# INPUT_8CH.net
KiCad netlist of a schematic drawn in Altium Designer
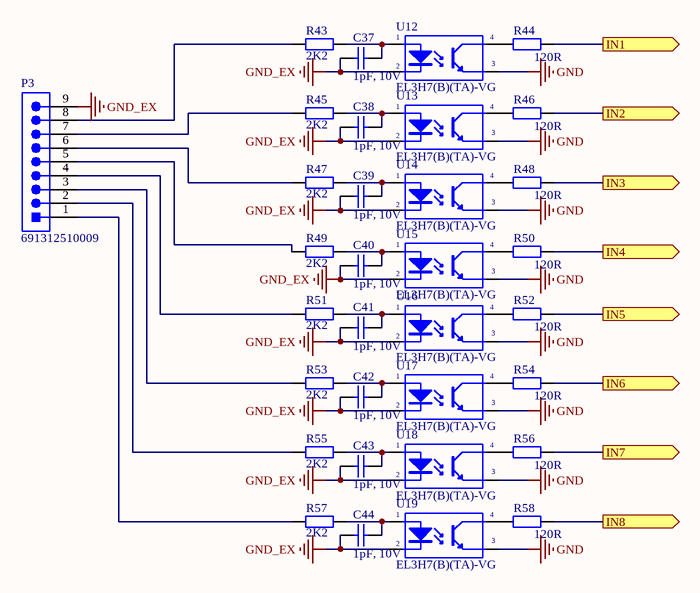
[diagram p0: INPUT_8CH.SchDoc]

(export (version "E")
  (design (tool "Eeschema 10.0.6"))
  (components
    (comp (ref "C37")
      (value "1pF, 10V")
      (footprint "CAP_0805")
      (description "WCAP-CSGP General Purpose Ceramic Capacitors")
      (fields (field (name "PART NUMBER") "885012005001") (field (name "PUBLISHER") "Wurth Elektronik"))
      (libsource (lib "ThanhNhan") (part "CAP_SMD"))
    )
    (comp (ref "C38")
      (value "1pF, 10V")
      (footprint "CAP_0805")
      (description "WCAP-CSGP General Purpose Ceramic Capacitors")
      (fields (field (name "PART NUMBER") "885012005001") (field (name "PUBLISHER") "Wurth Elektronik"))
      (libsource (lib "ThanhNhan") (part "CAP_SMD"))
    )
    (comp (ref "C39")
      (value "1pF, 10V")
      (footprint "CAP_0805")
      (description "WCAP-CSGP General Purpose Ceramic Capacitors")
      (fields (field (name "PART NUMBER") "885012005001") (field (name "PUBLISHER") "Wurth Elektronik"))
      (libsource (lib "ThanhNhan") (part "CAP_SMD"))
    )
    (comp (ref "C40")
      (value "1pF, 10V")
      (footprint "CAP_0805")
      (description "WCAP-CSGP General Purpose Ceramic Capacitors")
      (fields (field (name "PART NUMBER") "885012005001") (field (name "PUBLISHER") "Wurth Elektronik"))
      (libsource (lib "ThanhNhan") (part "CAP_SMD"))
    )
    (comp (ref "C41")
      (value "1pF, 10V")
      (footprint "CAP_0805")
      (description "WCAP-CSGP General Purpose Ceramic Capacitors")
      (fields (field (name "PART NUMBER") "885012005001") (field (name "PUBLISHER") "Wurth Elektronik"))
      (libsource (lib "ThanhNhan") (part "CAP_SMD"))
    )
    (comp (ref "C42")
      (value "1pF, 10V")
      (footprint "CAP_0805")
      (description "WCAP-CSGP General Purpose Ceramic Capacitors")
      (fields (field (name "PART NUMBER") "885012005001") (field (name "PUBLISHER") "Wurth Elektronik"))
      (libsource (lib "ThanhNhan") (part "CAP_SMD"))
    )
    (comp (ref "C43")
      (value "1pF, 10V")
      (footprint "CAP_0805")
      (description "WCAP-CSGP General Purpose Ceramic Capacitors")
      (fields (field (name "PART NUMBER") "885012005001") (field (name "PUBLISHER") "Wurth Elektronik"))
      (libsource (lib "ThanhNhan") (part "CAP_SMD"))
    )
    (comp (ref "C44")
      (value "1pF, 10V")
      (footprint "CAP_0805")
      (description "WCAP-CSGP General Purpose Ceramic Capacitors")
      (fields (field (name "PART NUMBER") "885012005001") (field (name "PUBLISHER") "Wurth Elektronik"))
      (libsource (lib "ThanhNhan") (part "CAP_SMD"))
    )
    (comp (ref "P3")
      (value "691312510009")
      (footprint "691312510009")
      (description "WR-TBL Serie 312 Open Horizontal PCB Header, Pluggable, THT, pitch 5.08mm, 9p")
      (fields (field (name "MANUFACTURER") "Wurth Elektronik"))
      (libsource (lib "Integrated_Library1") (part "691312510009"))
    )
    (comp (ref "R43")
      (value "2K2")
      (footprint "RES_1206")
      (description "WRIS-KSKE SMT Thick Film Resistor, 0.125W")
      (fields
        (field (name "MANUFACTURER") "Wurth Elektronik")
        (field (name "MANUFACTURER PART NUMBER") "560050310010")
      )
      (libsource (lib "ThanhNhan") (part "RES_SMD"))
    )
    (comp (ref "R44")
      (value "120R")
      (footprint "RES_0603")
      (description "WRIS-KSKE SMT Thick Film Resistor, 0.125W")
      (fields
        (field (name "MANUFACTURER") "Wurth Elektronik")
        (field (name "MANUFACTURER PART NUMBER") "560050310010")
      )
      (libsource (lib "ThanhNhan") (part "RES_SMD"))
    )
    (comp (ref "R45")
      (value "2K2")
      (footprint "RES_1206")
      (description "WRIS-KSKE SMT Thick Film Resistor, 0.125W")
      (fields
        (field (name "MANUFACTURER") "Wurth Elektronik")
        (field (name "MANUFACTURER PART NUMBER") "560050310010")
      )
      (libsource (lib "ThanhNhan") (part "RES_SMD"))
    )
    (comp (ref "R46")
      (value "120R")
      (footprint "RES_0603")
      (description "WRIS-KSKE SMT Thick Film Resistor, 0.125W")
      (fields
        (field (name "MANUFACTURER") "Wurth Elektronik")
        (field (name "MANUFACTURER PART NUMBER") "560050310010")
      )
      (libsource (lib "ThanhNhan") (part "RES_SMD"))
    )
    (comp (ref "R47")
      (value "2K2")
      (footprint "RES_1206")
      (description "WRIS-KSKE SMT Thick Film Resistor, 0.125W")
      (fields
        (field (name "MANUFACTURER") "Wurth Elektronik")
        (field (name "MANUFACTURER PART NUMBER") "560050310010")
      )
      (libsource (lib "ThanhNhan") (part "RES_SMD"))
    )
    (comp (ref "R48")
      (value "120R")
      (footprint "RES_0603")
      (description "WRIS-KSKE SMT Thick Film Resistor, 0.125W")
      (fields
        (field (name "MANUFACTURER") "Wurth Elektronik")
        (field (name "MANUFACTURER PART NUMBER") "560050310010")
      )
      (libsource (lib "ThanhNhan") (part "RES_SMD"))
    )
    (comp (ref "R49")
      (value "2K2")
      (footprint "RES_1206")
      (description "WRIS-KSKE SMT Thick Film Resistor, 0.125W")
      (fields
        (field (name "MANUFACTURER") "Wurth Elektronik")
        (field (name "MANUFACTURER PART NUMBER") "560050310010")
      )
      (libsource (lib "ThanhNhan") (part "RES_SMD"))
    )
    (comp (ref "R50")
      (value "120R")
      (footprint "RES_0603")
      (description "WRIS-KSKE SMT Thick Film Resistor, 0.125W")
      (fields
        (field (name "MANUFACTURER") "Wurth Elektronik")
        (field (name "MANUFACTURER PART NUMBER") "560050310010")
      )
      (libsource (lib "ThanhNhan") (part "RES_SMD"))
    )
    (comp (ref "R51")
      (value "2K2")
      (footprint "RES_1206")
      (description "WRIS-KSKE SMT Thick Film Resistor, 0.125W")
      (fields
        (field (name "MANUFACTURER") "Wurth Elektronik")
        (field (name "MANUFACTURER PART NUMBER") "560050310010")
      )
      (libsource (lib "ThanhNhan") (part "RES_SMD"))
    )
    (comp (ref "R52")
      (value "120R")
      (footprint "RES_0603")
      (description "WRIS-KSKE SMT Thick Film Resistor, 0.125W")
      (fields
        (field (name "MANUFACTURER") "Wurth Elektronik")
        (field (name "MANUFACTURER PART NUMBER") "560050310010")
      )
      (libsource (lib "ThanhNhan") (part "RES_SMD"))
    )
    (comp (ref "R53")
      (value "2K2")
      (footprint "RES_1206")
      (description "WRIS-KSKE SMT Thick Film Resistor, 0.125W")
      (fields
        (field (name "MANUFACTURER") "Wurth Elektronik")
        (field (name "MANUFACTURER PART NUMBER") "560050310010")
      )
      (libsource (lib "ThanhNhan") (part "RES_SMD"))
    )
    (comp (ref "R54")
      (value "120R")
      (footprint "RES_0603")
      (description "WRIS-KSKE SMT Thick Film Resistor, 0.125W")
      (fields
        (field (name "MANUFACTURER") "Wurth Elektronik")
        (field (name "MANUFACTURER PART NUMBER") "560050310010")
      )
      (libsource (lib "ThanhNhan") (part "RES_SMD"))
    )
    (comp (ref "R55")
      (value "2K2")
      (footprint "RES_1206")
      (description "WRIS-KSKE SMT Thick Film Resistor, 0.125W")
      (fields
        (field (name "MANUFACTURER") "Wurth Elektronik")
        (field (name "MANUFACTURER PART NUMBER") "560050310010")
      )
      (libsource (lib "ThanhNhan") (part "RES_SMD"))
    )
    (comp (ref "R56")
      (value "120R")
      (footprint "RES_0603")
      (description "WRIS-KSKE SMT Thick Film Resistor, 0.125W")
      (fields
        (field (name "MANUFACTURER") "Wurth Elektronik")
        (field (name "MANUFACTURER PART NUMBER") "560050310010")
      )
      (libsource (lib "ThanhNhan") (part "RES_SMD"))
    )
    (comp (ref "R57")
      (value "2K2")
      (footprint "RES_1206")
      (description "WRIS-KSKE SMT Thick Film Resistor, 0.125W")
      (fields
        (field (name "MANUFACTURER") "Wurth Elektronik")
        (field (name "MANUFACTURER PART NUMBER") "560050310010")
      )
      (libsource (lib "ThanhNhan") (part "RES_SMD"))
    )
    (comp (ref "R58")
      (value "120R")
      (footprint "RES_0603")
      (description "WRIS-KSKE SMT Thick Film Resistor, 0.125W")
      (fields
        (field (name "MANUFACTURER") "Wurth Elektronik")
        (field (name "MANUFACTURER PART NUMBER") "560050310010")
      )
      (libsource (lib "ThanhNhan") (part "RES_SMD"))
    )
    (comp (ref "U12")
      (value "UNK_Everlight_EL3H7_B_TA_-VG_eec")
      (footprint "Everlight_EL3H7_B_TA_-VG_0")
      (description "UNK OPTOISOLATOR 3.75KV TRANS 4-SSOP")
      (fields
        (field (name "MANUFACTURER") "Everlight")
        (field (name "MOUSER PART NUMBER") "638-EL3H7BTAVG")
        (field (name "PART NUMBER") "EL3H7(B)(TA)-VG")
      )
      (libsource (lib "myAltium") (part "UNK_Everlight_EL3H7_B_TA_-VG_eec"))
    )
    (comp (ref "U13")
      (value "UNK_Everlight_EL3H7_B_TA_-VG_eec")
      (footprint "Everlight_EL3H7_B_TA_-VG_0")
      (description "UNK OPTOISOLATOR 3.75KV TRANS 4-SSOP")
      (fields
        (field (name "MANUFACTURER") "Everlight")
        (field (name "MOUSER PART NUMBER") "638-EL3H7BTAVG")
        (field (name "PART NUMBER") "EL3H7(B)(TA)-VG")
      )
      (libsource (lib "myAltium") (part "UNK_Everlight_EL3H7_B_TA_-VG_eec"))
    )
    (comp (ref "U14")
      (value "UNK_Everlight_EL3H7_B_TA_-VG_eec")
      (footprint "Everlight_EL3H7_B_TA_-VG_0")
      (description "UNK OPTOISOLATOR 3.75KV TRANS 4-SSOP")
      (fields
        (field (name "MANUFACTURER") "Everlight")
        (field (name "MOUSER PART NUMBER") "638-EL3H7BTAVG")
        (field (name "PART NUMBER") "EL3H7(B)(TA)-VG")
      )
      (libsource (lib "myAltium") (part "UNK_Everlight_EL3H7_B_TA_-VG_eec"))
    )
    (comp (ref "U15")
      (value "UNK_Everlight_EL3H7_B_TA_-VG_eec")
      (footprint "Everlight_EL3H7_B_TA_-VG_0")
      (description "UNK OPTOISOLATOR 3.75KV TRANS 4-SSOP")
      (fields
        (field (name "MANUFACTURER") "Everlight")
        (field (name "MOUSER PART NUMBER") "638-EL3H7BTAVG")
        (field (name "PART NUMBER") "EL3H7(B)(TA)-VG")
      )
      (libsource (lib "myAltium") (part "UNK_Everlight_EL3H7_B_TA_-VG_eec"))
    )
    (comp (ref "U16")
      (value "UNK_Everlight_EL3H7_B_TA_-VG_eec")
      (footprint "Everlight_EL3H7_B_TA_-VG_0")
      (description "UNK OPTOISOLATOR 3.75KV TRANS 4-SSOP")
      (fields
        (field (name "MANUFACTURER") "Everlight")
        (field (name "MOUSER PART NUMBER") "638-EL3H7BTAVG")
        (field (name "PART NUMBER") "EL3H7(B)(TA)-VG")
      )
      (libsource (lib "myAltium") (part "UNK_Everlight_EL3H7_B_TA_-VG_eec"))
    )
    (comp (ref "U17")
      (value "UNK_Everlight_EL3H7_B_TA_-VG_eec")
      (footprint "Everlight_EL3H7_B_TA_-VG_0")
      (description "UNK OPTOISOLATOR 3.75KV TRANS 4-SSOP")
      (fields
        (field (name "MANUFACTURER") "Everlight")
        (field (name "MOUSER PART NUMBER") "638-EL3H7BTAVG")
        (field (name "PART NUMBER") "EL3H7(B)(TA)-VG")
      )
      (libsource (lib "myAltium") (part "UNK_Everlight_EL3H7_B_TA_-VG_eec"))
    )
    (comp (ref "U18")
      (value "UNK_Everlight_EL3H7_B_TA_-VG_eec")
      (footprint "Everlight_EL3H7_B_TA_-VG_0")
      (description "UNK OPTOISOLATOR 3.75KV TRANS 4-SSOP")
      (fields
        (field (name "MANUFACTURER") "Everlight")
        (field (name "MOUSER PART NUMBER") "638-EL3H7BTAVG")
        (field (name "PART NUMBER") "EL3H7(B)(TA)-VG")
      )
      (libsource (lib "myAltium") (part "UNK_Everlight_EL3H7_B_TA_-VG_eec"))
    )
    (comp (ref "U19")
      (value "UNK_Everlight_EL3H7_B_TA_-VG_eec")
      (footprint "Everlight_EL3H7_B_TA_-VG_0")
      (description "UNK OPTOISOLATOR 3.75KV TRANS 4-SSOP")
      (fields
        (field (name "MANUFACTURER") "Everlight")
        (field (name "MOUSER PART NUMBER") "638-EL3H7BTAVG")
        (field (name "PART NUMBER") "EL3H7(B)(TA)-VG")
      )
      (libsource (lib "myAltium") (part "UNK_Everlight_EL3H7_B_TA_-VG_eec"))
    )
  )
  (nets
    (net (code "1") (name "/IN1") (class "Default")
      (node (ref "R44") (pin "2") (pinfunction "2_2") (pintype "passive"))
    )
    (net (code "2") (name "/IN2") (class "Default")
      (node (ref "R46") (pin "2") (pinfunction "2_2") (pintype "passive"))
    )
    (net (code "3") (name "/IN3") (class "Default")
      (node (ref "R48") (pin "2") (pinfunction "2_2") (pintype "passive"))
    )
    (net (code "4") (name "/IN4") (class "Default")
      (node (ref "R50") (pin "2") (pinfunction "2_2") (pintype "passive"))
    )
    (net (code "5") (name "/IN5") (class "Default")
      (node (ref "R52") (pin "2") (pinfunction "2_2") (pintype "passive"))
    )
    (net (code "6") (name "/IN6") (class "Default")
      (node (ref "R54") (pin "2") (pinfunction "2_2") (pintype "passive"))
    )
    (net (code "7") (name "/IN7") (class "Default")
      (node (ref "R56") (pin "2") (pinfunction "2_2") (pintype "passive"))
    )
    (net (code "8") (name "/IN8") (class "Default")
      (node (ref "R58") (pin "2") (pinfunction "2_2") (pintype "passive"))
    )
    (net (code "9") (name "GND") (class "Default")
      (node (ref "U12") (pin "3") (pinfunction "E_3") (pintype "passive"))
      (node (ref "U13") (pin "3") (pinfunction "E_3") (pintype "passive"))
      (node (ref "U14") (pin "3") (pinfunction "E_3") (pintype "passive"))
      (node (ref "U15") (pin "3") (pinfunction "E_3") (pintype "passive"))
      (node (ref "U16") (pin "3") (pinfunction "E_3") (pintype "passive"))
      (node (ref "U17") (pin "3") (pinfunction "E_3") (pintype "passive"))
      (node (ref "U18") (pin "3") (pinfunction "E_3") (pintype "passive"))
      (node (ref "U19") (pin "3") (pinfunction "E_3") (pintype "passive"))
    )
    (net (code "10") (name "GND_EX") (class "Default")
      (node (ref "C37") (pin "1") (pinfunction "1_1") (pintype "passive"))
      (node (ref "C38") (pin "1") (pinfunction "1_1") (pintype "passive"))
      (node (ref "C39") (pin "1") (pinfunction "1_1") (pintype "passive"))
      (node (ref "C40") (pin "1") (pinfunction "1_1") (pintype "passive"))
      (node (ref "C41") (pin "1") (pinfunction "1_1") (pintype "passive"))
      (node (ref "C42") (pin "1") (pinfunction "1_1") (pintype "passive"))
      (node (ref "C43") (pin "1") (pinfunction "1_1") (pintype "passive"))
      (node (ref "C44") (pin "1") (pinfunction "1_1") (pintype "passive"))
      (node (ref "P3") (pin "9") (pinfunction "9_9") (pintype "passive"))
      (node (ref "U12") (pin "2") (pinfunction "K_2") (pintype "passive"))
      (node (ref "U13") (pin "2") (pinfunction "K_2") (pintype "passive"))
      (node (ref "U14") (pin "2") (pinfunction "K_2") (pintype "passive"))
      (node (ref "U15") (pin "2") (pinfunction "K_2") (pintype "passive"))
      (node (ref "U16") (pin "2") (pinfunction "K_2") (pintype "passive"))
      (node (ref "U17") (pin "2") (pinfunction "K_2") (pintype "passive"))
      (node (ref "U18") (pin "2") (pinfunction "K_2") (pintype "passive"))
      (node (ref "U19") (pin "2") (pinfunction "K_2") (pintype "passive"))
    )
    (net (code "11") (name "Net-(P3-Pad1)") (class "Default")
      (node (ref "P3") (pin "1") (pinfunction "1_1") (pintype "passive"))
      (node (ref "R57") (pin "1") (pinfunction "1_1") (pintype "passive"))
    )
    (net (code "12") (name "Net-(P3-Pad2)") (class "Default")
      (node (ref "P3") (pin "2") (pinfunction "2_2") (pintype "passive"))
      (node (ref "R55") (pin "1") (pinfunction "1_1") (pintype "passive"))
    )
    (net (code "13") (name "Net-(P3-Pad3)") (class "Default")
      (node (ref "P3") (pin "3") (pinfunction "3_3") (pintype "passive"))
      (node (ref "R53") (pin "1") (pinfunction "1_1") (pintype "passive"))
    )
    (net (code "14") (name "Net-(P3-Pad4)") (class "Default")
      (node (ref "P3") (pin "4") (pinfunction "4_4") (pintype "passive"))
      (node (ref "R51") (pin "1") (pinfunction "1_1") (pintype "passive"))
    )
    (net (code "15") (name "Net-(P3-Pad5)") (class "Default")
      (node (ref "P3") (pin "5") (pinfunction "5_5") (pintype "passive"))
      (node (ref "R49") (pin "1") (pinfunction "1_1") (pintype "passive"))
    )
    (net (code "16") (name "Net-(P3-Pad6)") (class "Default")
      (node (ref "P3") (pin "6") (pinfunction "6_6") (pintype "passive"))
      (node (ref "R47") (pin "1") (pinfunction "1_1") (pintype "passive"))
    )
    (net (code "17") (name "Net-(P3-Pad7)") (class "Default")
      (node (ref "P3") (pin "7") (pinfunction "7_7") (pintype "passive"))
      (node (ref "R45") (pin "1") (pinfunction "1_1") (pintype "passive"))
    )
    (net (code "18") (name "Net-(P3-Pad8)") (class "Default")
      (node (ref "P3") (pin "8") (pinfunction "8_8") (pintype "passive"))
      (node (ref "R43") (pin "1") (pinfunction "1_1") (pintype "passive"))
    )
    (net (code "19") (name "Net-(U12-A)") (class "Default")
      (node (ref "C37") (pin "2") (pinfunction "2_2") (pintype "passive"))
      (node (ref "R43") (pin "2") (pinfunction "2_2") (pintype "passive"))
      (node (ref "U12") (pin "1") (pinfunction "A_1") (pintype "passive"))
    )
    (net (code "20") (name "Net-(U12-C)") (class "Default")
      (node (ref "R44") (pin "1") (pinfunction "1_1") (pintype "passive"))
      (node (ref "U12") (pin "4") (pinfunction "C_4") (pintype "passive"))
    )
    (net (code "21") (name "Net-(U13-A)") (class "Default")
      (node (ref "C38") (pin "2") (pinfunction "2_2") (pintype "passive"))
      (node (ref "R45") (pin "2") (pinfunction "2_2") (pintype "passive"))
      (node (ref "U13") (pin "1") (pinfunction "A_1") (pintype "passive"))
    )
    (net (code "22") (name "Net-(U13-C)") (class "Default")
      (node (ref "R46") (pin "1") (pinfunction "1_1") (pintype "passive"))
      (node (ref "U13") (pin "4") (pinfunction "C_4") (pintype "passive"))
    )
    (net (code "23") (name "Net-(U14-A)") (class "Default")
      (node (ref "C39") (pin "2") (pinfunction "2_2") (pintype "passive"))
      (node (ref "R47") (pin "2") (pinfunction "2_2") (pintype "passive"))
      (node (ref "U14") (pin "1") (pinfunction "A_1") (pintype "passive"))
    )
    (net (code "24") (name "Net-(U14-C)") (class "Default")
      (node (ref "R48") (pin "1") (pinfunction "1_1") (pintype "passive"))
      (node (ref "U14") (pin "4") (pinfunction "C_4") (pintype "passive"))
    )
    (net (code "25") (name "Net-(U15-A)") (class "Default")
      (node (ref "C40") (pin "2") (pinfunction "2_2") (pintype "passive"))
      (node (ref "R49") (pin "2") (pinfunction "2_2") (pintype "passive"))
      (node (ref "U15") (pin "1") (pinfunction "A_1") (pintype "passive"))
    )
    (net (code "26") (name "Net-(U15-C)") (class "Default")
      (node (ref "R50") (pin "1") (pinfunction "1_1") (pintype "passive"))
      (node (ref "U15") (pin "4") (pinfunction "C_4") (pintype "passive"))
    )
    (net (code "27") (name "Net-(U16-A)") (class "Default")
      (node (ref "C41") (pin "2") (pinfunction "2_2") (pintype "passive"))
      (node (ref "R51") (pin "2") (pinfunction "2_2") (pintype "passive"))
      (node (ref "U16") (pin "1") (pinfunction "A_1") (pintype "passive"))
    )
    (net (code "28") (name "Net-(U16-C)") (class "Default")
      (node (ref "R52") (pin "1") (pinfunction "1_1") (pintype "passive"))
      (node (ref "U16") (pin "4") (pinfunction "C_4") (pintype "passive"))
    )
    (net (code "29") (name "Net-(U17-A)") (class "Default")
      (node (ref "C42") (pin "2") (pinfunction "2_2") (pintype "passive"))
      (node (ref "R53") (pin "2") (pinfunction "2_2") (pintype "passive"))
      (node (ref "U17") (pin "1") (pinfunction "A_1") (pintype "passive"))
    )
    (net (code "30") (name "Net-(U17-C)") (class "Default")
      (node (ref "R54") (pin "1") (pinfunction "1_1") (pintype "passive"))
      (node (ref "U17") (pin "4") (pinfunction "C_4") (pintype "passive"))
    )
    (net (code "31") (name "Net-(U18-A)") (class "Default")
      (node (ref "C43") (pin "2") (pinfunction "2_2") (pintype "passive"))
      (node (ref "R55") (pin "2") (pinfunction "2_2") (pintype "passive"))
      (node (ref "U18") (pin "1") (pinfunction "A_1") (pintype "passive"))
    )
    (net (code "32") (name "Net-(U18-C)") (class "Default")
      (node (ref "R56") (pin "1") (pinfunction "1_1") (pintype "passive"))
      (node (ref "U18") (pin "4") (pinfunction "C_4") (pintype "passive"))
    )
    (net (code "33") (name "Net-(U19-A)") (class "Default")
      (node (ref "C44") (pin "2") (pinfunction "2_2") (pintype "passive"))
      (node (ref "R57") (pin "2") (pinfunction "2_2") (pintype "passive"))
      (node (ref "U19") (pin "1") (pinfunction "A_1") (pintype "passive"))
    )
    (net (code "34") (name "Net-(U19-C)") (class "Default")
      (node (ref "R58") (pin "1") (pinfunction "1_1") (pintype "passive"))
      (node (ref "U19") (pin "4") (pinfunction "C_4") (pintype "passive"))
    )
  )
)
